# Mech_Interface_Starboard_Deployable.net
KiCad netlist of a schematic drawn in Altium Designer
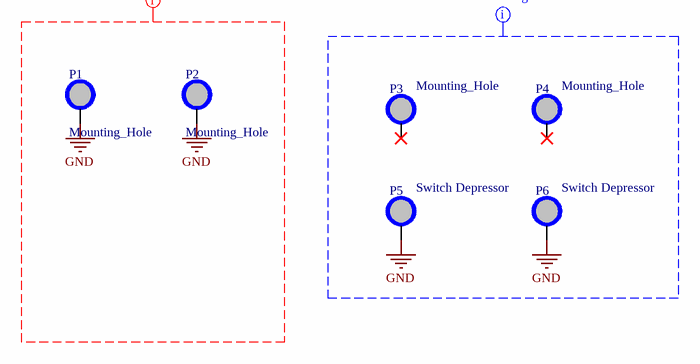
[diagram p0: Mech_Interface_Starboard_Deployable.SchDoc]

(export (version "E")
  (design (tool "Eeschema 10.0.6"))
  (components
    (comp (ref "P1")
      (value "Mounting_Hole")
      (footprint "Burnwire_Screw_Small_Foot")
      (fields
        (field (name "PART NUMBER") "PXX-ABS-00016")
        (field (name "MANUFACTURER PART NUMBER") "Custom")
        (field (name "PUBLISHER") "AlbertaSat")
      )
      (libsource (lib "Database") (part "Mounting_Hole"))
    )
    (comp (ref "P2")
      (value "Mounting_Hole")
      (footprint "Burnwire_Screw_Small_Foot")
      (fields
        (field (name "PART NUMBER") "PXX-ABS-00016")
        (field (name "MANUFACTURER PART NUMBER") "Custom")
        (field (name "PUBLISHER") "AlbertaSat")
      )
      (libsource (lib "Database") (part "Mounting_Hole"))
    )
    (comp (ref "P3")
      (value "Mounting_Hole")
      (footprint "DepHinge_Mounting_Hole")
      (description "Depolyable Hinge Mounting hole.")
      (fields (field (name "PART NUMBER") "PXX-ABS-00003") (field (name "PUBLISHER") "AlbertaSat"))
      (libsource (lib "Database") (part "Mounting_Hole"))
    )
    (comp (ref "P4")
      (value "Mounting_Hole")
      (footprint "DepHinge_Mounting_Hole")
      (description "Depolyable Hinge Mounting hole.")
      (fields (field (name "PART NUMBER") "PXX-ABS-00003") (field (name "PUBLISHER") "AlbertaSat"))
      (libsource (lib "Database") (part "Mounting_Hole"))
    )
    (comp (ref "P5")
      (value "Switch Depressor")
      (footprint "Switch_Depressor")
      (description "Hardware for depressing the switch")
      (fields
        (field (name "PART NUMBER") "PXX-ABS-00005")
        (field (name "MANUFACTURER PART NUMBER") "Custom")
        (field (name "PUBLISHER") "AlbertaSat")
      )
      (libsource (lib "Database") (part "Mounting_Hole"))
    )
    (comp (ref "P6")
      (value "Switch Depressor")
      (footprint "Switch_Depressor")
      (description "Hardware for depressing the switch")
      (fields
        (field (name "PART NUMBER") "PXX-ABS-00005")
        (field (name "MANUFACTURER PART NUMBER") "Custom")
        (field (name "PUBLISHER") "AlbertaSat")
      )
      (libsource (lib "Database") (part "Mounting_Hole"))
    )
  )
  (nets
    (net (code "1") (name "GND") (class "Default")
      (node (ref "P1") (pin "1") (pinfunction "0_1") (pintype "passive"))
      (node (ref "P2") (pin "1") (pinfunction "0_1") (pintype "passive"))
      (node (ref "P5") (pin "1") (pinfunction "0_1") (pintype "passive"))
      (node (ref "P6") (pin "1") (pinfunction "0_1") (pintype "passive"))
    )
    (net (code "2") (name "unconnected-(P3-0-Pad1)") (class "Default")
      (node (ref "P3") (pin "1") (pinfunction "0_1") (pintype "passive+no_connect"))
    )
    (net (code "3") (name "unconnected-(P4-0-Pad1)") (class "Default")
      (node (ref "P4") (pin "1") (pinfunction "0_1") (pintype "passive+no_connect"))
    )
  )
)
